# Antenna.net
KiCad netlist of a schematic drawn in Altium Designer
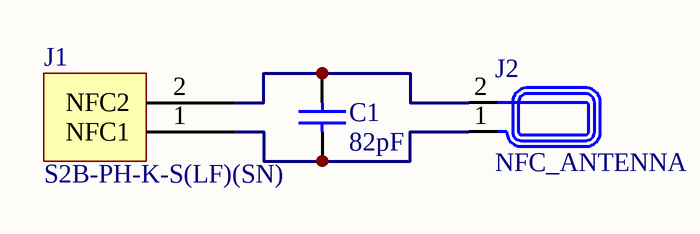
[diagram p0: Antenna.SchDoc]

(export (version "E")
  (design (tool "Eeschema 10.0.6"))
  (components
    (comp (ref "C1")
      (value "82pF")
      (footprint "CAPC1608X08N")
      (description "Cap Ceramic 82pF 50V C0G 5% SMD 0603 125C Paper T/R")
      (fields
        (field (name "MANUFACTURER") "Samsung")
        (field (name "MANUFACTURER PART NUMBER") "CL10C820JB8NNNC")
      )
      (libsource (lib "Components") (part "CL10C820JB8NNNC"))
    )
    (comp (ref "J1")
      (value "S2B-PH-K-S(LF)(SN)")
      (footprint "S2B-PH-K-S")
      (description "2 Positions Header, Shrouded Connector 0.079\" (2.00mm) Through Hole, Right Angle Tin")
      (fields (field (name "MANUFACTURER") "JST"))
      (libsource (lib "Components") (part "S2B-PH-K-S(LF)(SN)"))
    )
    (comp (ref "J2")
      (value "NFC_ANTENNA")
      (footprint "NFC_ANTENNA")
      (libsource (lib "Components") (part "NFC_ANTENNA"))
    )
  )
  (nets
    (net (code "1") (name "Net-(J1-NFC1)") (class "Default")
      (node (ref "C1") (pin "1") (pinfunction "1_1") (pintype "passive"))
      (node (ref "J1") (pin "1") (pinfunction "NFC1_1") (pintype "power_in"))
      (node (ref "J2") (pin "1") (pinfunction "NFC1_1") (pintype "passive"))
    )
    (net (code "2") (name "Net-(J1-NFC2)") (class "Default")
      (node (ref "C1") (pin "2") (pinfunction "2_2") (pintype "passive"))
      (node (ref "J1") (pin "2") (pinfunction "NFC2_2") (pintype "power_in"))
      (node (ref "J2") (pin "2") (pinfunction "NFC2_2") (pintype "passive"))
    )
  )
)
